# openSX70_PATHFINDER_V5_5-SEEED_20180522.net
KiCad netlist of a schematic drawn in EAGLE
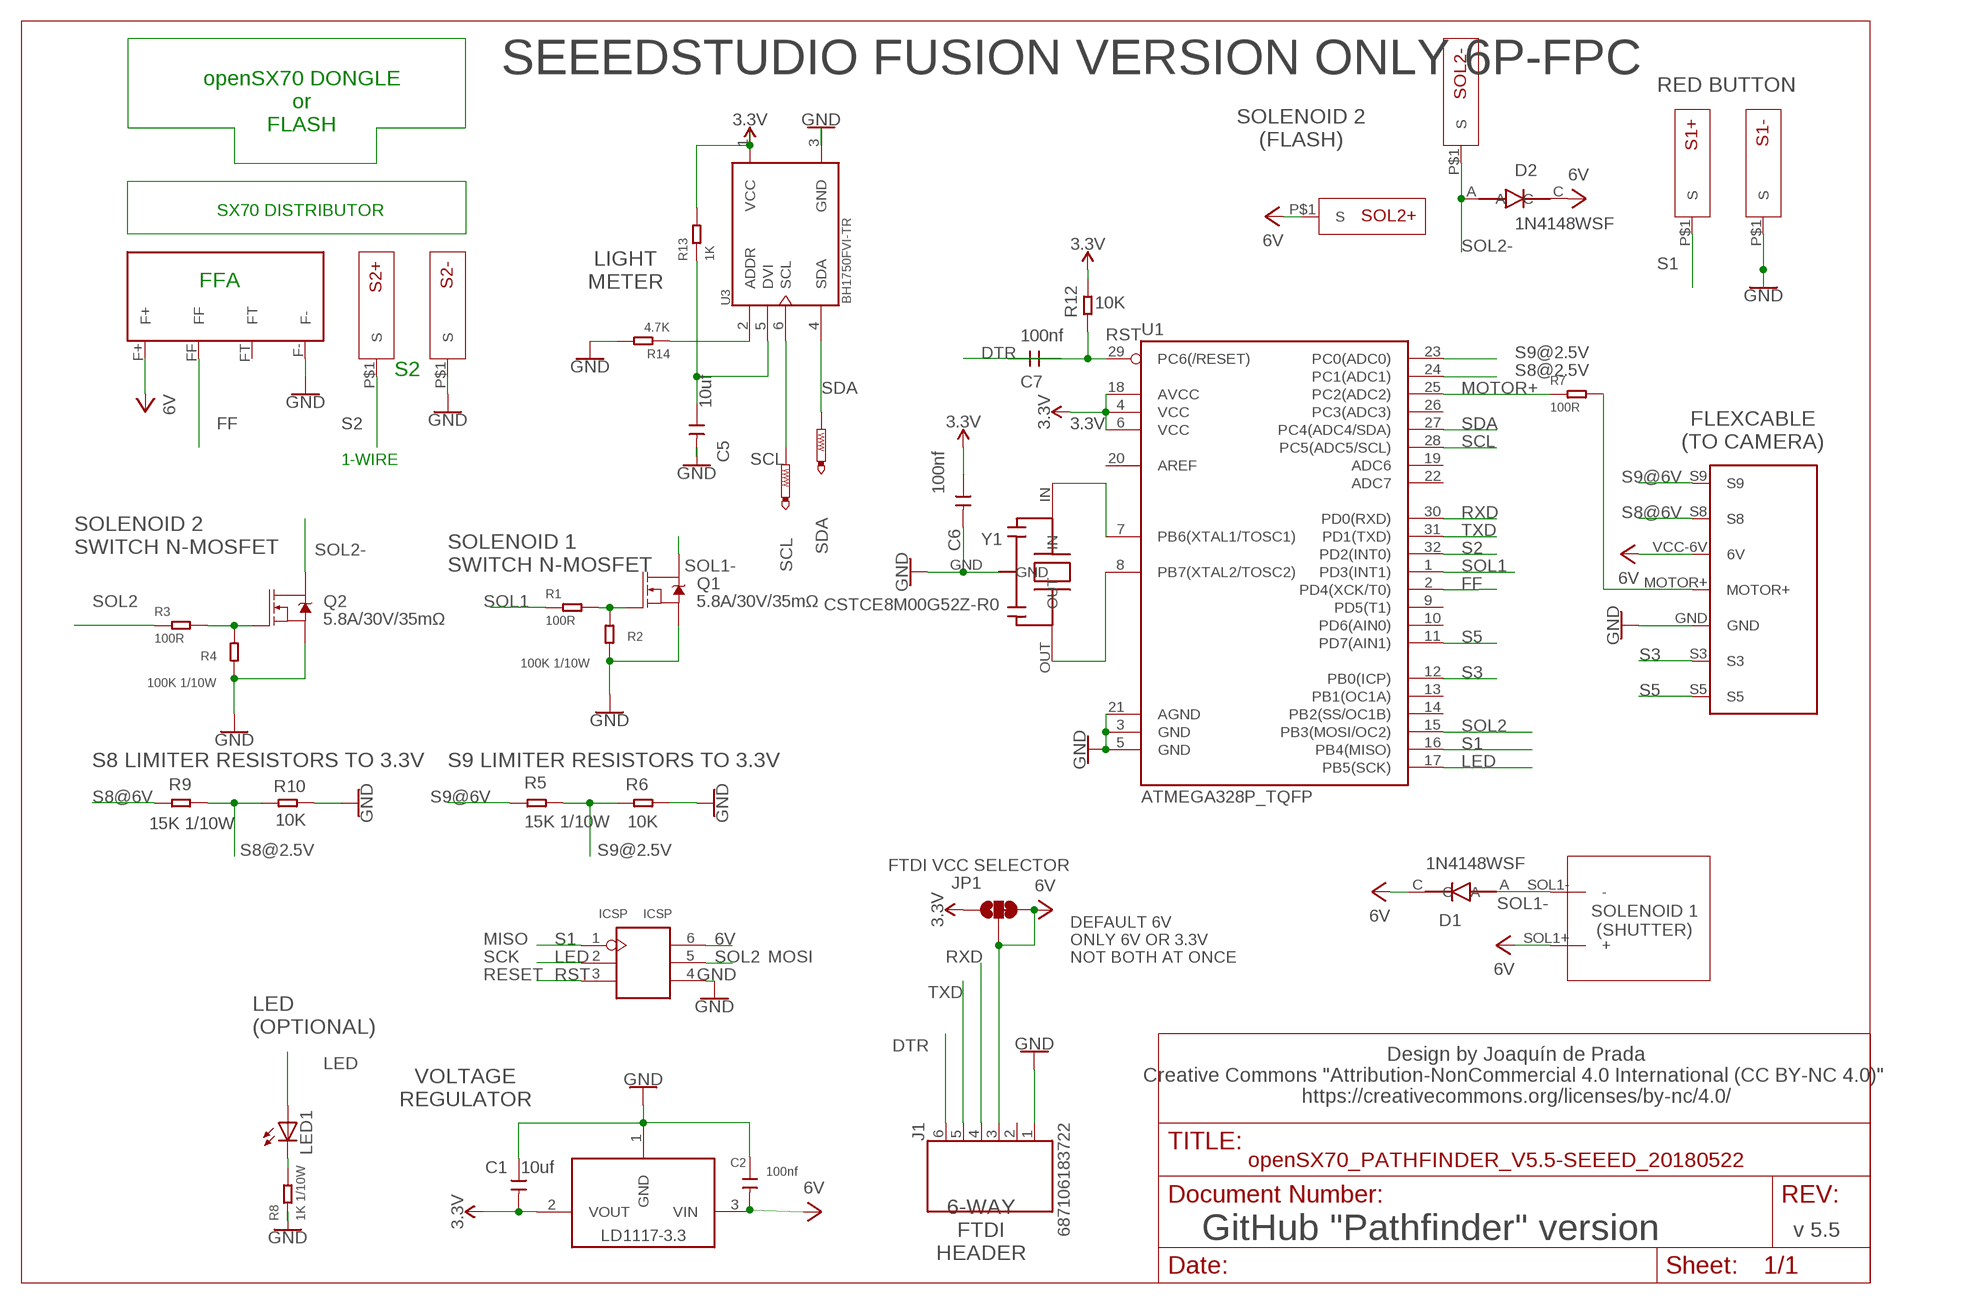
[diagram p0: schematic, sheet 1]

(export (version "E")
  (design (tool "Eeschema 10.0.6"))
  (components
    (comp (ref "C1")
      (value "10uf")
      (footprint "eagle-import:C0603")
      (fields (field (name "MPN") "CC0603KRX5R6BB106"))
      (libsource (lib "eagle-import") (part "CERAMIC-10UF-10V-10%-X5R(0603)"))
    )
    (comp (ref "C2")
      (value "100nf")
      (footprint "eagle-import:C0603")
      (fields (field (name "MPN") "CC0603KRX7R9BB104"))
      (libsource (lib "eagle-import") (part "CERAMIC-100NF-50V-10%-X7R(0603)"))
    )
    (comp (ref "C5")
      (value "10uf")
      (footprint "eagle-import:C0603")
      (fields (field (name "MPN") "CC0603KRX5R6BB106"))
      (libsource (lib "eagle-import") (part "CERAMIC-10UF-10V-10%-X5R(0603)"))
    )
    (comp (ref "C6")
      (value "100nf")
      (footprint "eagle-import:C0603")
      (fields (field (name "MPN") "CC0603KRX7R9BB104"))
      (libsource (lib "eagle-import") (part "CERAMIC-100NF-50V-10%-X7R(0603)"))
    )
    (comp (ref "C7")
      (value "100nf")
      (footprint "eagle-import:C0603")
      (fields (field (name "MPN") "CC0603KRX7R9BB104"))
      (libsource (lib "eagle-import") (part "CERAMIC-100NF-50V-10%-X7R(0603)"))
    )
    (comp (ref "D1")
      (value "1N4148WSF")
      (footprint "eagle-import:SODFL2512X100N")
      (fields (field (name "MANUFACTURER") "Fairchild Semiconductor"))
      (libsource (lib "eagle-import") (part "1N4148WS"))
    )
    (comp (ref "D2")
      (value "1N4148WSF")
      (footprint "eagle-import:SODFL2512X100N")
      (fields (field (name "MANUFACTURER") "Fairchild Semiconductor"))
      (libsource (lib "eagle-import") (part "1N4148WS"))
    )
    (comp (ref "ICSP")
      (value "ICSP")
      (footprint "eagle-import:H2X3-2.54")
      (libsource (lib "eagle-import") (part "ICSP"))
    )
    (comp (ref "J1")
      (value "687106183722")
      (footprint "eagle-import:687106183722")
      (fields (field (name "MF") "Wurth Electronics"))
      (libsource (lib "eagle-import") (part "687106183722"))
    )
    (comp (ref "JP1")
      (value "FTDI VCC SELECTOR")
      (footprint "eagle-import:SMT-JUMPER_3_1-NC_TRACE_SILK")
      (libsource (lib "eagle-import") (part "JUMPER-SMT_3_1-NC_TRACE_SILK"))
    )
    (comp (ref "LD11172.5V")
      (value "LD1117 2.5V")
      (footprint "eagle-import:SOT223")
      (fields (field (name "MF") "Advanced Monolithic Systems") (field (name "MP") "AMS1117-5.0"))
      (libsource (lib "eagle-import") (part "LD1117-3.3"))
    )
    (comp (ref "LED1")
      (value "LEDCHIPLED_0805")
      (footprint "eagle-import:CHIPLED_0805")
      (libsource (lib "eagle-import") (part "LEDCHIPLED_0805"))
    )
    (comp (ref "Q1")
      (value "5.8A/30V/35mΩ")
      (footprint "eagle-import:SOT23-3")
      (libsource (lib "eagle-import") (part "MOSFET-NCH-AO3404A"))
    )
    (comp (ref "Q2")
      (value "5.8A/30V/35mΩ")
      (footprint "eagle-import:SOT23-3")
      (libsource (lib "eagle-import") (part "MOSFET-NCH-AO3404A"))
    )
    (comp (ref "R1")
      (value "100R")
      (footprint "eagle-import:R0603")
      (fields (field (name "MPN") "RC0603JR-07100RL"))
      (libsource (lib "eagle-import") (part "SMD-RES-100R-5%-1/10W(0603)"))
    )
    (comp (ref "R2")
      (value "100K 1/10W")
      (footprint "eagle-import:R0603")
      (fields (field (name "MPN") "RC0603JR-07100KL"))
      (libsource (lib "eagle-import") (part "SMD-RES-100K-5%-1/10W(0603)"))
    )
    (comp (ref "R3")
      (value "100R")
      (footprint "eagle-import:R0603")
      (fields (field (name "MPN") "RC0603JR-07100RL"))
      (libsource (lib "eagle-import") (part "SMD-RES-100R-5%-1/10W(0603)"))
    )
    (comp (ref "R4")
      (value "100K 1/10W")
      (footprint "eagle-import:R0603")
      (fields (field (name "MPN") "RC0603JR-07100KL"))
      (libsource (lib "eagle-import") (part "SMD-RES-100K-5%-1/10W(0603)"))
    )
    (comp (ref "R5")
      (value "15K 1/10W")
      (footprint "eagle-import:R0603")
      (fields (field (name "MPN") "RC0603FR-0715KL"))
      (libsource (lib "eagle-import") (part "SMD-RES-15K-1%-1/10W(0603)"))
    )
    (comp (ref "R6")
      (value "10K")
      (footprint "eagle-import:R0603")
      (fields (field (name "MPN") "RC0603FR-0710KL"))
      (libsource (lib "eagle-import") (part "SMD-RES-10K-1%-1/10W(0603)"))
    )
    (comp (ref "R7")
      (value "100R")
      (footprint "eagle-import:R0603")
      (fields (field (name "MPN") "RC0603JR-07100RL"))
      (libsource (lib "eagle-import") (part "SMD-RES-100R-5%-1/10W(0603)"))
    )
    (comp (ref "R8")
      (value "1K 1/10W")
      (footprint "eagle-import:R0603")
      (fields (field (name "MPN") "RC0603JR-071KL"))
      (libsource (lib "eagle-import") (part "SMD-RES-1K-5%-1/10W(0603)"))
    )
    (comp (ref "R9")
      (value "15K 1/10W")
      (footprint "eagle-import:R0603")
      (fields (field (name "MPN") "RC0603FR-0715KL"))
      (libsource (lib "eagle-import") (part "SMD-RES-15K-1%-1/10W(0603)"))
    )
    (comp (ref "R10")
      (value "10K")
      (footprint "eagle-import:R0603")
      (fields (field (name "MPN") "RC0603FR-0710KL"))
      (libsource (lib "eagle-import") (part "SMD-RES-10K-1%-1/10W(0603)"))
    )
    (comp (ref "R12")
      (value "10K")
      (footprint "eagle-import:R0603")
      (fields (field (name "MPN") "RC0603FR-0710KL"))
      (libsource (lib "eagle-import") (part "SMD-RES-10K-1%-1/10W(0603)"))
    )
    (comp (ref "R13")
      (value "1K")
      (footprint "eagle-import:R0603")
      (fields (field (name "MPN") "RC0603FR-071KL"))
      (libsource (lib "eagle-import") (part "SMD-RES-1K-1%-1/10W(0603)"))
    )
    (comp (ref "R14")
      (value "4.7K")
      (footprint "eagle-import:R0603")
      (fields (field (name "MPN") "RC0603JR-074K7L"))
      (libsource (lib "eagle-import") (part "SMD-RES-4.7K-5%-1/10W(0603)"))
    )
    (comp (ref "S1+")
      (value "SX70-S-PAD-NEW")
      (footprint "eagle-import:SX70-S-PAD2")
      (libsource (lib "eagle-import") (part "SX70-S-PAD-NEW"))
    )
    (comp (ref "S1-")
      (value "SX70-S-PAD-NEW")
      (footprint "eagle-import:SX70-S-PAD2")
      (libsource (lib "eagle-import") (part "SX70-S-PAD-NEW"))
    )
    (comp (ref "S2+")
      (value "SX70-S-PAD-NEW")
      (footprint "eagle-import:SX70-S-PAD2")
      (libsource (lib "eagle-import") (part "SX70-S-PAD-NEW"))
    )
    (comp (ref "S2-")
      (value "SX70-S-PAD-NEW")
      (footprint "eagle-import:SX70-S-PAD2")
      (libsource (lib "eagle-import") (part "SX70-S-PAD-NEW"))
    )
    (comp (ref "SCL")
      (value "PTR1TP08R")
      (footprint "eagle-import:TP08R")
      (libsource (lib "eagle-import") (part "PTR1TP08R"))
    )
    (comp (ref "SDA")
      (value "PTR1TP08R")
      (footprint "eagle-import:TP08R")
      (libsource (lib "eagle-import") (part "PTR1TP08R"))
    )
    (comp (ref "SOL1")
      (value "SX70-SOLENOID1-2PADS")
      (footprint "eagle-import:SX70-SOLENOID1-2")
      (libsource (lib "eagle-import") (part "SX70-SOLENOID1-2PADS"))
    )
    (comp (ref "SOL2+")
      (value "SX70-S-PAD-NEW")
      (footprint "eagle-import:SX70-S-PAD2")
      (libsource (lib "eagle-import") (part "SX70-S-PAD-NEW"))
    )
    (comp (ref "SOL2-")
      (value "SX70-S-PAD-NEW")
      (footprint "eagle-import:SX70-S-PAD2")
      (libsource (lib "eagle-import") (part "SX70-S-PAD-NEW"))
    )
    (comp (ref "U$1")
      (value "SX70-7-PAD")
      (footprint "eagle-import:SX70-7-PAD")
      (libsource (lib "eagle-import") (part "SX70-7-PAD"))
    )
    (comp (ref "U$2")
      (value "FFA")
      (footprint "eagle-import:FFA-PAD-PACKAGE")
      (libsource (lib "eagle-import") (part "SX70-FFA-PAD"))
    )
    (comp (ref "U1")
      (value "ATMEGA328P_TQFP")
      (footprint "eagle-import:TQFP32-08")
      (libsource (lib "eagle-import") (part "ATMEGA328P_TQFP"))
    )
    (comp (ref "U3")
      (value "BH1750FVI-TR")
      (footprint "eagle-import:SOTFL50P300X75-6N")
      (fields (field (name "MF") "Rohm"))
      (libsource (lib "eagle-import") (part "BH1750FVI-TR"))
    )
    (comp (ref "Y1")
      (value "CSTCE8M00G52Z-R0")
      (footprint "eagle-import:CFP95P160X100-3N")
      (fields (field (name "MF") "Murata") (field (name "MP") "CSTCE16M0V53-R0"))
      (libsource (lib "eagle-import") (part "CSTCE16M0V53-R0"))
    )
  )
  (nets
    (net (code "1") (name "/DTR") (class "Default")
      (node (ref "C7") (pin "1") (pinfunction "1_1") (pintype "passive"))
      (node (ref "J1") (pin "6") (pinfunction "1_6") (pintype "passive"))
    )
    (net (code "2") (name "/FF") (class "Default")
      (node (ref "U$2") (pin "FF") (pinfunction "FF_FF") (pintype "bidirectional"))
      (node (ref "U1") (pin "2") (pinfunction "PD4(XCK/T0)_2") (pintype "bidirectional"))
    )
    (net (code "3") (name "/LED") (class "Default")
      (node (ref "ICSP") (pin "2") (pinfunction "SCK_2") (pintype "bidirectional"))
      (node (ref "LED1") (pin "A") (pinfunction "A_A") (pintype "passive"))
      (node (ref "U1") (pin "17") (pinfunction "PB5(SCK)_17") (pintype "bidirectional"))
    )
    (net (code "4") (name "/MOTOR+") (class "Default")
      (node (ref "R7") (pin "1") (pinfunction "1_1") (pintype "passive"))
      (node (ref "U1") (pin "25") (pinfunction "PC2(ADC2)_25") (pintype "bidirectional"))
    )
    (net (code "5") (name "/RST") (class "Default")
      (node (ref "C7") (pin "2") (pinfunction "2_2") (pintype "passive"))
      (node (ref "ICSP") (pin "3") (pinfunction "RST_3") (pintype "bidirectional"))
      (node (ref "R12") (pin "1") (pinfunction "1_1") (pintype "passive"))
      (node (ref "U1") (pin "29") (pinfunction "PC6(/RESET)_29") (pintype "bidirectional"))
    )
    (net (code "6") (name "/RXD") (class "Default")
      (node (ref "J1") (pin "4") (pinfunction "3_4") (pintype "passive"))
      (node (ref "U1") (pin "30") (pinfunction "PD0(RXD)_30") (pintype "bidirectional"))
    )
    (net (code "7") (name "/S1") (class "Default")
      (node (ref "ICSP") (pin "1") (pinfunction "MISO_1") (pintype "bidirectional"))
      (node (ref "S1+") (pin "P$1") (pinfunction "S_P$1") (pintype "bidirectional"))
      (node (ref "U1") (pin "16") (pinfunction "PB4(MISO)_16") (pintype "bidirectional"))
    )
    (net (code "8") (name "/S2") (class "Default")
      (node (ref "S2+") (pin "P$1") (pinfunction "S_P$1") (pintype "bidirectional"))
      (node (ref "U1") (pin "32") (pinfunction "PD2(INT0)_32") (pintype "bidirectional"))
    )
    (net (code "9") (name "/S3") (class "Default")
      (node (ref "U$1") (pin "S3") (pinfunction "S3_S3") (pintype "bidirectional"))
      (node (ref "U1") (pin "12") (pinfunction "PB0(ICP)_12") (pintype "bidirectional"))
    )
    (net (code "10") (name "/S5") (class "Default")
      (node (ref "U$1") (pin "S5") (pinfunction "S5_S5") (pintype "bidirectional"))
      (node (ref "U1") (pin "11") (pinfunction "PD7(AIN1)_11") (pintype "bidirectional"))
    )
    (net (code "11") (name "/S8@2.5V") (class "Default")
      (node (ref "R10") (pin "1") (pinfunction "1_1") (pintype "passive"))
      (node (ref "R9") (pin "2") (pinfunction "2_2") (pintype "passive"))
      (node (ref "U1") (pin "24") (pinfunction "PC1(ADC1)_24") (pintype "bidirectional"))
    )
    (net (code "12") (name "/S8@6V") (class "Default")
      (node (ref "R9") (pin "1") (pinfunction "1_1") (pintype "passive"))
      (node (ref "U$1") (pin "S8") (pinfunction "S8_S8") (pintype "bidirectional"))
    )
    (net (code "13") (name "/S9@2.5V") (class "Default")
      (node (ref "R5") (pin "2") (pinfunction "2_2") (pintype "passive"))
      (node (ref "R6") (pin "1") (pinfunction "1_1") (pintype "passive"))
      (node (ref "U1") (pin "23") (pinfunction "PC0(ADC0)_23") (pintype "bidirectional"))
    )
    (net (code "14") (name "/S9@6V") (class "Default")
      (node (ref "R5") (pin "1") (pinfunction "1_1") (pintype "passive"))
      (node (ref "U$1") (pin "S9") (pinfunction "S9_S9") (pintype "bidirectional"))
    )
    (net (code "15") (name "/SCL") (class "Default")
      (node (ref "SCL") (pin "TP") (pinfunction "TP_TP") (pintype "input"))
      (node (ref "U1") (pin "28") (pinfunction "PC5(ADC5/SCL)_28") (pintype "bidirectional"))
      (node (ref "U3") (pin "6") (pinfunction "SCL_6") (pintype "input"))
    )
    (net (code "16") (name "/SDA") (class "Default")
      (node (ref "SDA") (pin "TP") (pinfunction "TP_TP") (pintype "input"))
      (node (ref "U1") (pin "27") (pinfunction "PC4(ADC4/SDA)_27") (pintype "bidirectional"))
      (node (ref "U3") (pin "4") (pinfunction "SDA_4") (pintype "bidirectional"))
    )
    (net (code "17") (name "/SOL1") (class "Default")
      (node (ref "R1") (pin "1") (pinfunction "1_1") (pintype "passive"))
      (node (ref "U1") (pin "1") (pinfunction "PD3(INT1)_1") (pintype "bidirectional"))
    )
    (net (code "18") (name "/SOL1-") (class "Default")
      (node (ref "D1") (pin "A") (pinfunction "A_A") (pintype "passive"))
      (node (ref "Q1") (pin "3") (pinfunction "D_3") (pintype "bidirectional"))
      (node (ref "SOL1") (pin "SOL1-") (pinfunction "-_SOL1-") (pintype "bidirectional"))
    )
    (net (code "19") (name "/SOL2") (class "Default")
      (node (ref "ICSP") (pin "5") (pinfunction "MOSI_5") (pintype "bidirectional"))
      (node (ref "R3") (pin "1") (pinfunction "1_1") (pintype "passive"))
      (node (ref "U1") (pin "15") (pinfunction "PB3(MOSI/OC2)_15") (pintype "bidirectional"))
    )
    (net (code "20") (name "/SOL2-") (class "Default")
      (node (ref "D2") (pin "A") (pinfunction "A_A") (pintype "passive"))
      (node (ref "Q2") (pin "3") (pinfunction "D_3") (pintype "bidirectional"))
      (node (ref "SOL2-") (pin "P$1") (pinfunction "S_P$1") (pintype "bidirectional"))
    )
    (net (code "21") (name "/TXD") (class "Default")
      (node (ref "J1") (pin "5") (pinfunction "2_5") (pintype "passive"))
      (node (ref "U1") (pin "31") (pinfunction "PD1(TXD)_31") (pintype "bidirectional"))
    )
    (net (code "22") (name "3.3V") (class "Default")
      (node (ref "C1") (pin "2") (pinfunction "2_2") (pintype "passive"))
      (node (ref "C6") (pin "1") (pinfunction "1_1") (pintype "passive"))
      (node (ref "JP1") (pin "1") (pinfunction "1_1") (pintype "passive"))
      (node (ref "LD11172.5V") (pin "2") (pinfunction "VOUT_2") (pintype "bidirectional"))
      (node (ref "R12") (pin "2") (pinfunction "2_2") (pintype "passive"))
      (node (ref "R13") (pin "2") (pinfunction "2_2") (pintype "passive"))
      (node (ref "U1") (pin "18") (pinfunction "AVCC_18") (pintype "bidirectional"))
      (node (ref "U1") (pin "4") (pinfunction "VCC_4") (pintype "bidirectional"))
      (node (ref "U1") (pin "6") (pinfunction "VCC_6") (pintype "bidirectional"))
      (node (ref "U3") (pin "1") (pinfunction "VCC_1") (pintype "power_in"))
    )
    (net (code "23") (name "6V") (class "Default")
      (node (ref "C2") (pin "2") (pinfunction "2_2") (pintype "passive"))
      (node (ref "D1") (pin "C") (pinfunction "C_C") (pintype "passive"))
      (node (ref "D2") (pin "C") (pinfunction "C_C") (pintype "passive"))
      (node (ref "ICSP") (pin "6") (pinfunction "VCC_6") (pintype "bidirectional"))
      (node (ref "J1") (pin "3") (pinfunction "4_3") (pintype "passive"))
      (node (ref "JP1") (pin "2") (pinfunction "2_2") (pintype "passive"))
      (node (ref "JP1") (pin "3") (pinfunction "3_3") (pintype "passive"))
      (node (ref "LD11172.5V") (pin "3") (pinfunction "VIN_3") (pintype "bidirectional"))
      (node (ref "SOL1") (pin "SOL1+") (pinfunction "+_SOL1+") (pintype "bidirectional"))
      (node (ref "SOL2+") (pin "P$1") (pinfunction "S_P$1") (pintype "bidirectional"))
      (node (ref "U$1") (pin "VCC-6V") (pinfunction "6V_VCC-6V") (pintype "bidirectional"))
      (node (ref "U$2") (pin "F+") (pinfunction "F+_F+") (pintype "bidirectional"))
    )
    (net (code "24") (name "GND") (class "Default")
      (node (ref "C1") (pin "1") (pinfunction "1_1") (pintype "passive"))
      (node (ref "C2") (pin "1") (pinfunction "1_1") (pintype "passive"))
      (node (ref "C5") (pin "2") (pinfunction "2_2") (pintype "passive"))
      (node (ref "C6") (pin "2") (pinfunction "2_2") (pintype "passive"))
      (node (ref "ICSP") (pin "4") (pinfunction "GND_4") (pintype "bidirectional"))
      (node (ref "J1") (pin "1") (pinfunction "6_1") (pintype "passive"))
      (node (ref "LD11172.5V") (pin "1") (pinfunction "GND_1") (pintype "bidirectional"))
      (node (ref "Q1") (pin "2") (pinfunction "S_2") (pintype "bidirectional"))
      (node (ref "Q2") (pin "2") (pinfunction "S_2") (pintype "bidirectional"))
      (node (ref "R10") (pin "2") (pinfunction "2_2") (pintype "passive"))
      (node (ref "R14") (pin "2") (pinfunction "2_2") (pintype "passive"))
      (node (ref "R2") (pin "1") (pinfunction "1_1") (pintype "passive"))
      (node (ref "R4") (pin "1") (pinfunction "1_1") (pintype "passive"))
      (node (ref "R6") (pin "2") (pinfunction "2_2") (pintype "passive"))
      (node (ref "R8") (pin "1") (pinfunction "1_1") (pintype "passive"))
      (node (ref "S1-") (pin "P$1") (pinfunction "S_P$1") (pintype "bidirectional"))
      (node (ref "S2-") (pin "P$1") (pinfunction "S_P$1") (pintype "bidirectional"))
      (node (ref "U$1") (pin "GND") (pinfunction "GND_GND") (pintype "bidirectional"))
      (node (ref "U$2") (pin "F-") (pinfunction "F-_F-") (pintype "bidirectional"))
      (node (ref "U1") (pin "21") (pinfunction "AGND_21") (pintype "bidirectional"))
      (node (ref "U1") (pin "3") (pinfunction "GND_3") (pintype "bidirectional"))
      (node (ref "U1") (pin "5") (pinfunction "GND_5") (pintype "bidirectional"))
      (node (ref "U3") (pin "3") (pinfunction "GND_3") (pintype "power_in"))
      (node (ref "Y1") (pin "GND") (pinfunction "GND_GND") (pintype "passive"))
    )
    (net (code "25") (name "Net-(LED1-PadC)") (class "Default")
      (node (ref "LED1") (pin "C") (pinfunction "C_C") (pintype "passive"))
      (node (ref "R8") (pin "2") (pinfunction "2_2") (pintype "passive"))
    )
    (net (code "26") (name "Net-(Q1-G)") (class "Default")
      (node (ref "Q1") (pin "1") (pinfunction "G_1") (pintype "bidirectional"))
      (node (ref "R1") (pin "2") (pinfunction "2_2") (pintype "passive"))
      (node (ref "R2") (pin "2") (pinfunction "2_2") (pintype "passive"))
    )
    (net (code "27") (name "Net-(Q2-G)") (class "Default")
      (node (ref "Q2") (pin "1") (pinfunction "G_1") (pintype "bidirectional"))
      (node (ref "R3") (pin "2") (pinfunction "2_2") (pintype "passive"))
      (node (ref "R4") (pin "2") (pinfunction "2_2") (pintype "passive"))
    )
    (net (code "28") (name "Net-(R7-Pad2)") (class "Default")
      (node (ref "R7") (pin "2") (pinfunction "2_2") (pintype "passive"))
      (node (ref "U$1") (pin "MOTOR+") (pinfunction "MOTOR+_MOTOR+") (pintype "bidirectional"))
    )
    (net (code "29") (name "Net-(U1-PB6(XTAL1{slash}TOSC1))") (class "Default")
      (node (ref "U1") (pin "7") (pinfunction "PB6(XTAL1/TOSC1)_7") (pintype "bidirectional"))
      (node (ref "Y1") (pin "IN") (pinfunction "IN_IN") (pintype "input"))
    )
    (net (code "30") (name "Net-(U1-PB7(XTAL2{slash}TOSC2))") (class "Default")
      (node (ref "U1") (pin "8") (pinfunction "PB7(XTAL2/TOSC2)_8") (pintype "bidirectional"))
      (node (ref "Y1") (pin "OUT") (pinfunction "OUT_OUT") (pintype "output"))
    )
    (net (code "31") (name "Net-(U3-ADDR)") (class "Default")
      (node (ref "R14") (pin "1") (pinfunction "1_1") (pintype "passive"))
      (node (ref "U3") (pin "2") (pinfunction "ADDR_2") (pintype "input"))
    )
    (net (code "32") (name "Net-(U3-DVI)") (class "Default")
      (node (ref "C5") (pin "1") (pinfunction "1_1") (pintype "passive"))
      (node (ref "R13") (pin "1") (pinfunction "1_1") (pintype "passive"))
      (node (ref "U3") (pin "5") (pinfunction "DVI_5") (pintype "input"))
    )
    (net (code "33") (name "unconnected-(J1-5-Pad2)") (class "Default")
      (node (ref "J1") (pin "2") (pinfunction "5_2") (pintype "passive"))
    )
    (net (code "34") (name "unconnected-(U$2-PadFT)") (class "Default")
      (node (ref "U$2") (pin "FT") (pinfunction "FT_FT") (pintype "bidirectional"))
    )
    (net (code "35") (name "unconnected-(U1-ADC6-Pad19)") (class "Default")
      (node (ref "U1") (pin "19") (pinfunction "ADC6_19") (pintype "bidirectional"))
    )
    (net (code "36") (name "unconnected-(U1-ADC7-Pad22)") (class "Default")
      (node (ref "U1") (pin "22") (pinfunction "ADC7_22") (pintype "bidirectional"))
    )
    (net (code "37") (name "unconnected-(U1-AREF-Pad20)") (class "Default")
      (node (ref "U1") (pin "20") (pinfunction "AREF_20") (pintype "bidirectional"))
    )
    (net (code "38") (name "unconnected-(U1-PB1(OC1A)-Pad13)") (class "Default")
      (node (ref "U1") (pin "13") (pinfunction "PB1(OC1A)_13") (pintype "bidirectional"))
    )
    (net (code "39") (name "unconnected-(U1-PB2(SS{slash}OC1B)-Pad14)") (class "Default")
      (node (ref "U1") (pin "14") (pinfunction "PB2(SS/OC1B)_14") (pintype "bidirectional"))
    )
    (net (code "40") (name "unconnected-(U1-PC3(ADC3)-Pad26)") (class "Default")
      (node (ref "U1") (pin "26") (pinfunction "PC3(ADC3)_26") (pintype "bidirectional"))
    )
    (net (code "41") (name "unconnected-(U1-PD5(T1)-Pad9)") (class "Default")
      (node (ref "U1") (pin "9") (pinfunction "PD5(T1)_9") (pintype "bidirectional"))
    )
    (net (code "42") (name "unconnected-(U1-PD6(AIN0)-Pad10)") (class "Default")
      (node (ref "U1") (pin "10") (pinfunction "PD6(AIN0)_10") (pintype "bidirectional"))
    )
  )
)
